# Communication_and_peripherals.net
KiCad netlist of a schematic drawn in Altium Designer
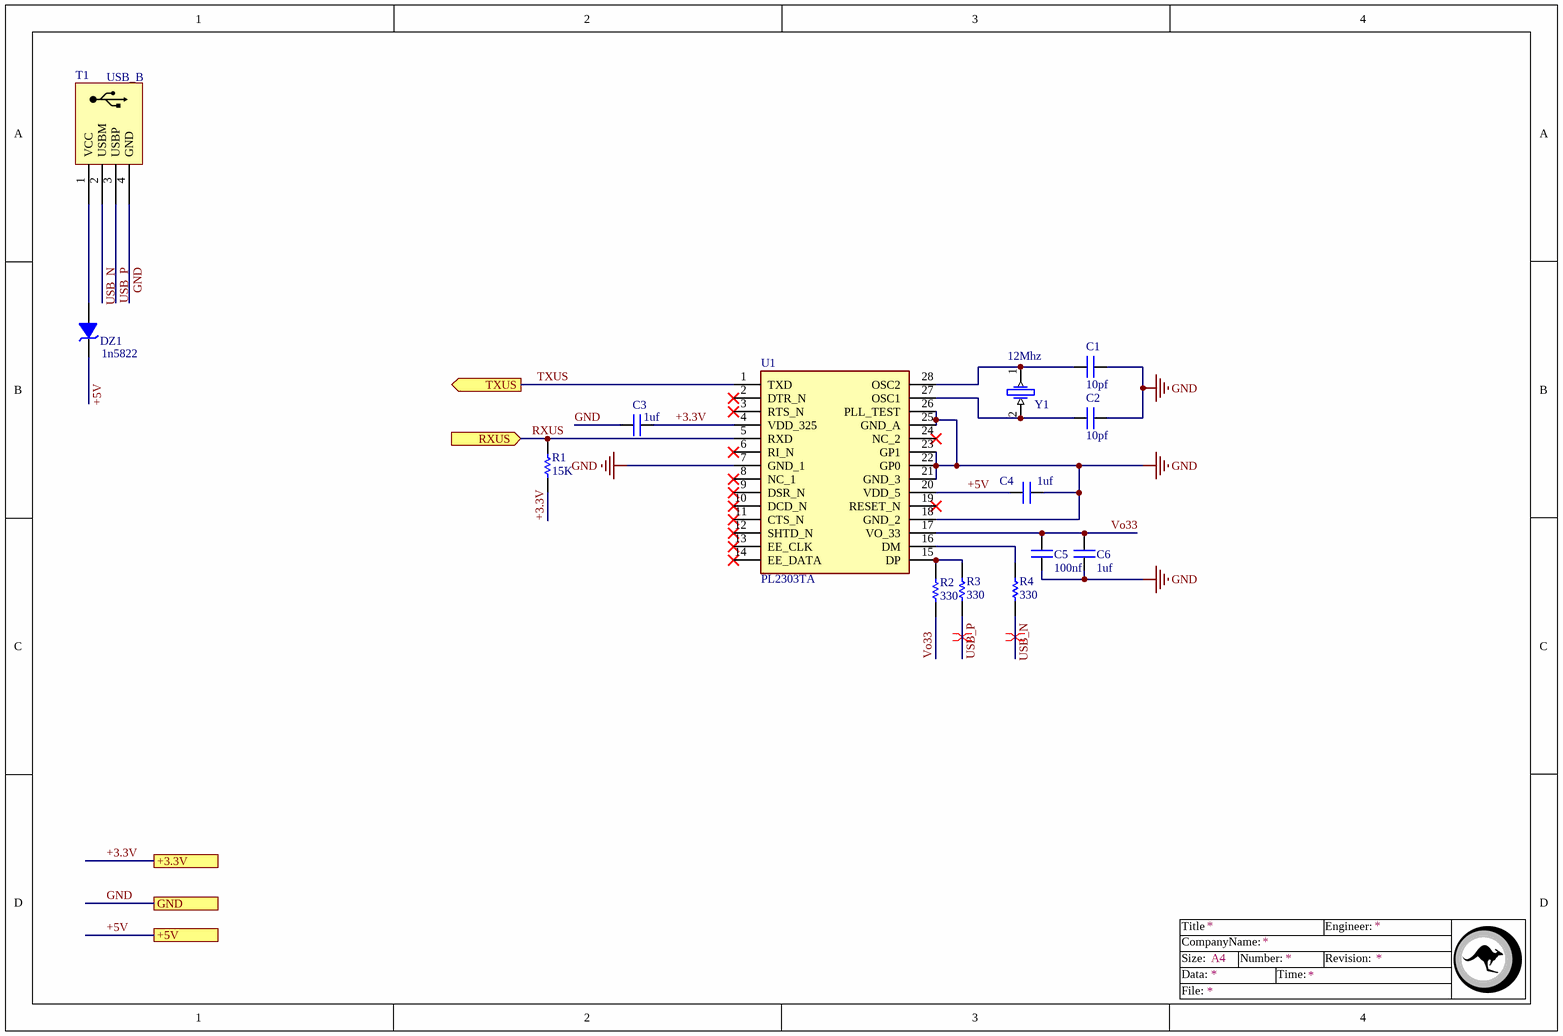
[diagram p0: Communication and peripherals.SchDoc]

(export (version "E")
  (design (tool "Eeschema 10.0.6"))
  (components
    (comp (ref "C1")
      (value "10pf")
      (footprint "Cap0805")
      (description "Surface mount Capacitor")
      (libsource (lib "PMLIB2020") (part "Cap"))
    )
    (comp (ref "C2")
      (value "10pf")
      (footprint "Cap0805")
      (description "Surface mount Capacitor")
      (libsource (lib "PMLIB2020") (part "Cap"))
    )
    (comp (ref "C3")
      (value "1uf")
      (footprint "Cap0805")
      (description "Surface mount Capacitor")
      (libsource (lib "PMLIB2020") (part "Cap"))
    )
    (comp (ref "C4")
      (value "1uf")
      (footprint "Cap0805")
      (description "Surface mount Capacitor")
      (libsource (lib "PMLIB2020") (part "Cap"))
    )
    (comp (ref "C5")
      (value "100nf")
      (footprint "Cap0805")
      (description "Surface mount Capacitor")
      (libsource (lib "PMLIB2020-V3") (part "Cap"))
    )
    (comp (ref "C6")
      (value "1uf")
      (footprint "Cap0805")
      (description "Surface mount Capacitor")
      (libsource (lib "PMLIB2020-V3") (part "Cap"))
    )
    (comp (ref "DZ1")
      (value "1n5822")
      (footprint "LL4148")
      (description "Diode Zener")
      (libsource (lib "PMLIB2020-V3") (part "Diode Zener"))
    )
    (comp (ref "R1")
      (value "15K")
      (footprint "R0805")
      (description "Resistor")
      (libsource (lib "PMLIB2020") (part "Resistor"))
    )
    (comp (ref "R2")
      (value "330")
      (footprint "R0805")
      (description "Resistor")
      (libsource (lib "PMLIB2020") (part "Resistor"))
    )
    (comp (ref "R3")
      (value "330")
      (footprint "R0805")
      (description "Resistor")
      (libsource (lib "PMLIB2020") (part "Resistor"))
    )
    (comp (ref "R4")
      (value "330")
      (footprint "R0805")
      (description "Resistor")
      (libsource (lib "PMLIB2020") (part "Resistor"))
    )
    (comp (ref "T1")
      (value "USB_B")
      (footprint "USB_Dip_R")
      (description "USB B Connector")
      (libsource (lib "PMLIB2020") (part "USB_B"))
    )
    (comp (ref "U1")
      (value "PL2303TA")
      (footprint "SOP65P780X200-28N")
      (description "Uart Chip")
      (libsource (lib "PMLIB2020-V3") (part "PL2303TA"))
    )
    (comp (ref "Y1")
      (value "12Mhz")
      (footprint "CrystallB")
      (description "Crystal")
      (libsource (lib "PMLIB2020") (part "Crystal"))
    )
  )
  (nets
    (net (code "1") (name "/+3.3V") (class "Default")
      (node (ref "C3") (pin "2") (pinfunction "2_2") (pintype "passive"))
      (node (ref "R1") (pin "1") (pinfunction "1_1") (pintype "passive"))
      (node (ref "U1") (pin "4") (pinfunction "VDD_325_4") (pintype "passive"))
    )
    (net (code "2") (name "/+5V") (class "Default")
      (node (ref "C4") (pin "2") (pinfunction "2_2") (pintype "passive"))
      (node (ref "DZ1") (pin "K") (pinfunction "K_K") (pintype "passive"))
      (node (ref "U1") (pin "20") (pinfunction "VDD_5_20") (pintype "passive"))
    )
    (net (code "3") (name "/RXUS") (class "Default")
      (node (ref "R1") (pin "2") (pinfunction "2_2") (pintype "passive"))
      (node (ref "U1") (pin "5") (pinfunction "RXD_5") (pintype "passive"))
    )
    (net (code "4") (name "/TXUS") (class "Default")
      (node (ref "U1") (pin "1") (pinfunction "TXD_1") (pintype "passive"))
    )
    (net (code "5") (name "/USB_N") (class "Default")
      (node (ref "R4") (pin "1") (pinfunction "1_1") (pintype "passive"))
      (node (ref "T1") (pin "2") (pinfunction "USBM_2") (pintype "passive"))
    )
    (net (code "6") (name "/USB_P") (class "Default")
      (node (ref "R3") (pin "1") (pinfunction "1_1") (pintype "passive"))
      (node (ref "T1") (pin "3") (pinfunction "USBP_3") (pintype "passive"))
    )
    (net (code "7") (name "/Vo33") (class "Default")
      (node (ref "C5") (pin "2") (pinfunction "2_2") (pintype "passive"))
      (node (ref "C6") (pin "2") (pinfunction "2_2") (pintype "passive"))
      (node (ref "R2") (pin "1") (pinfunction "1_1") (pintype "passive"))
      (node (ref "U1") (pin "17") (pinfunction "VO_33_17") (pintype "passive"))
    )
    (net (code "8") (name "GND") (class "Default")
      (node (ref "C1") (pin "2") (pinfunction "2_2") (pintype "passive"))
      (node (ref "C2") (pin "2") (pinfunction "2_2") (pintype "passive"))
      (node (ref "C3") (pin "1") (pinfunction "1_1") (pintype "passive"))
      (node (ref "C4") (pin "1") (pinfunction "1_1") (pintype "passive"))
      (node (ref "C5") (pin "1") (pinfunction "1_1") (pintype "passive"))
      (node (ref "C6") (pin "1") (pinfunction "1_1") (pintype "passive"))
      (node (ref "T1") (pin "4") (pinfunction "GND_4") (pintype "passive"))
      (node (ref "U1") (pin "18") (pinfunction "GND_2_18") (pintype "passive"))
      (node (ref "U1") (pin "21") (pinfunction "GND_3_21") (pintype "passive"))
      (node (ref "U1") (pin "22") (pinfunction "GP0_22") (pintype "passive"))
      (node (ref "U1") (pin "23") (pinfunction "GP1_23") (pintype "passive"))
      (node (ref "U1") (pin "25") (pinfunction "GND_A_25") (pintype "passive"))
      (node (ref "U1") (pin "26") (pinfunction "PLL_TEST_26") (pintype "passive"))
      (node (ref "U1") (pin "7") (pinfunction "GND_1_7") (pintype "passive"))
    )
    (net (code "9") (name "Net-(T1-VCC)") (class "Default")
      (node (ref "DZ1") (pin "A") (pinfunction "A_A") (pintype "passive"))
      (node (ref "T1") (pin "1") (pinfunction "VCC_1") (pintype "passive"))
    )
    (net (code "10") (name "Net-(U1-DM)") (class "Default")
      (node (ref "R4") (pin "2") (pinfunction "2_2") (pintype "passive"))
      (node (ref "U1") (pin "16") (pinfunction "DM_16") (pintype "passive"))
    )
    (net (code "11") (name "Net-(U1-DP)") (class "Default")
      (node (ref "R2") (pin "2") (pinfunction "2_2") (pintype "passive"))
      (node (ref "R3") (pin "2") (pinfunction "2_2") (pintype "passive"))
      (node (ref "U1") (pin "15") (pinfunction "DP_15") (pintype "passive"))
    )
    (net (code "12") (name "Net-(U1-OSC1)") (class "Default")
      (node (ref "C2") (pin "1") (pinfunction "1_1") (pintype "passive"))
      (node (ref "U1") (pin "27") (pinfunction "OSC1_27") (pintype "passive"))
      (node (ref "Y1") (pin "2") (pinfunction "2_2") (pintype "input"))
    )
    (net (code "13") (name "Net-(U1-OSC2)") (class "Default")
      (node (ref "C1") (pin "1") (pinfunction "1_1") (pintype "passive"))
      (node (ref "U1") (pin "28") (pinfunction "OSC2_28") (pintype "passive"))
      (node (ref "Y1") (pin "1") (pinfunction "1_1") (pintype "output"))
    )
    (net (code "14") (name "unconnected-(U1-CTS_N-Pad11)") (class "Default")
      (node (ref "U1") (pin "11") (pinfunction "CTS_N_11") (pintype "passive+no_connect"))
    )
    (net (code "15") (name "unconnected-(U1-DCD_N-Pad10)") (class "Default")
      (node (ref "U1") (pin "10") (pinfunction "DCD_N_10") (pintype "passive+no_connect"))
    )
    (net (code "16") (name "unconnected-(U1-DSR_N-Pad9)") (class "Default")
      (node (ref "U1") (pin "9") (pinfunction "DSR_N_9") (pintype "passive+no_connect"))
    )
    (net (code "17") (name "unconnected-(U1-DTR_N-Pad2)") (class "Default")
      (node (ref "U1") (pin "2") (pinfunction "DTR_N_2") (pintype "passive+no_connect"))
    )
    (net (code "18") (name "unconnected-(U1-EE_CLK-Pad13)") (class "Default")
      (node (ref "U1") (pin "13") (pinfunction "EE_CLK_13") (pintype "passive+no_connect"))
    )
    (net (code "19") (name "unconnected-(U1-EE_DATA-Pad14)") (class "Default")
      (node (ref "U1") (pin "14") (pinfunction "EE_DATA_14") (pintype "passive+no_connect"))
    )
    (net (code "20") (name "unconnected-(U1-NC_1-Pad8)") (class "Default")
      (node (ref "U1") (pin "8") (pinfunction "NC_1_8") (pintype "passive+no_connect"))
    )
    (net (code "21") (name "unconnected-(U1-NC_2-Pad24)") (class "Default")
      (node (ref "U1") (pin "24") (pinfunction "NC_2_24") (pintype "passive+no_connect"))
    )
    (net (code "22") (name "unconnected-(U1-RESET_N-Pad19)") (class "Default")
      (node (ref "U1") (pin "19") (pinfunction "RESET_N_19") (pintype "passive+no_connect"))
    )
    (net (code "23") (name "unconnected-(U1-RI_N-Pad6)") (class "Default")
      (node (ref "U1") (pin "6") (pinfunction "RI_N_6") (pintype "passive+no_connect"))
    )
    (net (code "24") (name "unconnected-(U1-RTS_N-Pad3)") (class "Default")
      (node (ref "U1") (pin "3") (pinfunction "RTS_N_3") (pintype "passive+no_connect"))
    )
    (net (code "25") (name "unconnected-(U1-SHTD_N-Pad12)") (class "Default")
      (node (ref "U1") (pin "12") (pinfunction "SHTD_N_12") (pintype "passive+no_connect"))
    )
  )
)
